# ldo_3v3.net
KiCad netlist of a schematic drawn in Altium Designer
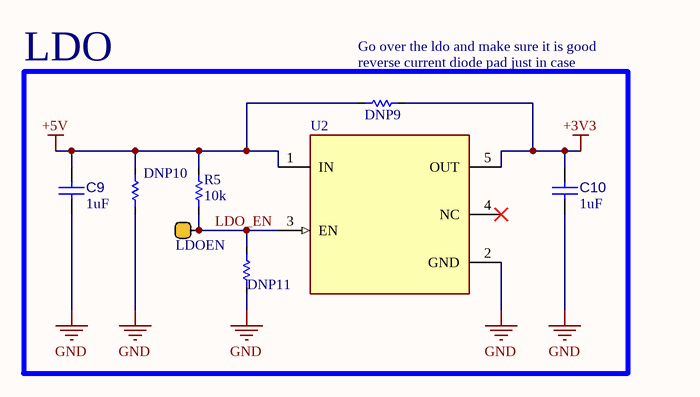
[diagram p0: ldo_3v3.SchDoc]

(export (version "E")
  (design (tool "Eeschema 10.0.6"))
  (components
    (comp (ref "C9")
      (value "1uF")
      (footprint "CAP_0603")
      (description "GCJ188R71E105KA01D - 1 µF ±10% 25V Ceramic Capacitor X7R 0603 (1608 Metric)")
      (fields (field (name "Comment") "CAP CER 220nF 50V 10% 0603"))
      (libsource (lib "power_board_schhlib") (part "C - CAP CER 1uF 25V 10% 0603"))
    )
    (comp (ref "C10")
      (value "1uF")
      (footprint "CAP_0603")
      (description "GCJ188R71E105KA01D - 1 µF ±10% 25V Ceramic Capacitor X7R 0603 (1608 Metric)")
      (fields (field (name "Comment") "CAP CER 220nF 50V 10% 0603"))
      (libsource (lib "power_board_schhlib") (part "C - CAP CER 1uF 25V 10% 0603"))
    )
    (comp (ref "DNP9")
      (value "DNP - DNP PAD 0603")
      (footprint "DNP 0603")
      (libsource (lib "power_board_schhlib") (part "DNP - DNP PAD 0603"))
    )
    (comp (ref "DNP10")
      (value "DNP - DNP PAD 0603")
      (footprint "DNP 0603")
      (libsource (lib "power_board_schhlib") (part "DNP - DNP PAD 0603"))
    )
    (comp (ref "DNP11")
      (value "DNP - DNP PAD 0603")
      (footprint "DNP 0603")
      (libsource (lib "power_board_schhlib") (part "DNP - DNP PAD 0603"))
    )
    (comp (ref "LDOEN")
      (value "TP - SMD Pad Testpoint-Symbol-1")
      (footprint "TP - SMD Pad Testpoint")
      (description "Testpoint used for debugging and testing. SMD Pad")
      (libsource (lib "power_board_schhlib") (part "TP - SMD Pad Testpoint-Symbol-1"))
    )
    (comp (ref "R5")
      (value "10k")
      (footprint "RES 0603")
      (fields (field (name "Comment") "R - RES 10kR 0.1W 1% 0603"))
      (libsource (lib "power_board_schhlib") (part "R - RES 10kR 0.1W 1% 0603"))
    )
    (comp (ref "U2")
      (value "TLV75733PDBVR")
      (footprint "U - TLV75733PDBVR")
      (fields (field (name "COPYRIGHT") "Copyright (C) 2025 Ultra Librarian. All rights reserved."))
      (libsource (lib "power_board_schhlib") (part "U - TLV75733PDBVR"))
    )
  )
  (nets
    (net (code "1") (name "+3V3") (class "Default")
      (node (ref "C10") (pin "2") (pinfunction "2_2") (pintype "passive"))
      (node (ref "DNP9") (pin "2") (pinfunction "2_2") (pintype "passive"))
      (node (ref "U2") (pin "5") (pinfunction "OUT_5") (pintype "power_in"))
    )
    (net (code "2") (name "+5V") (class "Default")
      (node (ref "C9") (pin "2") (pinfunction "2_2") (pintype "passive"))
      (node (ref "DNP10") (pin "2") (pinfunction "2_2") (pintype "passive"))
      (node (ref "DNP9") (pin "1") (pinfunction "1_1") (pintype "passive"))
      (node (ref "R5") (pin "2") (pinfunction "2_2") (pintype "passive"))
      (node (ref "U2") (pin "1") (pinfunction "IN_1") (pintype "power_in"))
    )
    (net (code "3") (name "/LDO_EN") (class "Default")
      (node (ref "DNP11") (pin "2") (pinfunction "2_2") (pintype "passive"))
      (node (ref "LDOEN") (pin "1") (pinfunction "1_1") (pintype "passive"))
      (node (ref "R5") (pin "1") (pinfunction "1_1") (pintype "passive"))
      (node (ref "U2") (pin "3") (pinfunction "EN_3") (pintype "input"))
    )
    (net (code "4") (name "GND") (class "Default")
      (node (ref "C10") (pin "1") (pinfunction "1_1") (pintype "passive"))
      (node (ref "C9") (pin "1") (pinfunction "1_1") (pintype "passive"))
      (node (ref "DNP10") (pin "1") (pinfunction "1_1") (pintype "passive"))
      (node (ref "DNP11") (pin "1") (pinfunction "1_1") (pintype "passive"))
      (node (ref "U2") (pin "2") (pinfunction "GND_2") (pintype "power_in"))
    )
    (net (code "5") (name "unconnected-(U2-NC-Pad4)") (class "Default")
      (node (ref "U2") (pin "4") (pinfunction "NC_4") (pintype "passive+no_connect"))
    )
  )
)
